# rs485_ISO_IO.net
KiCad netlist of a schematic drawn in EAGLE
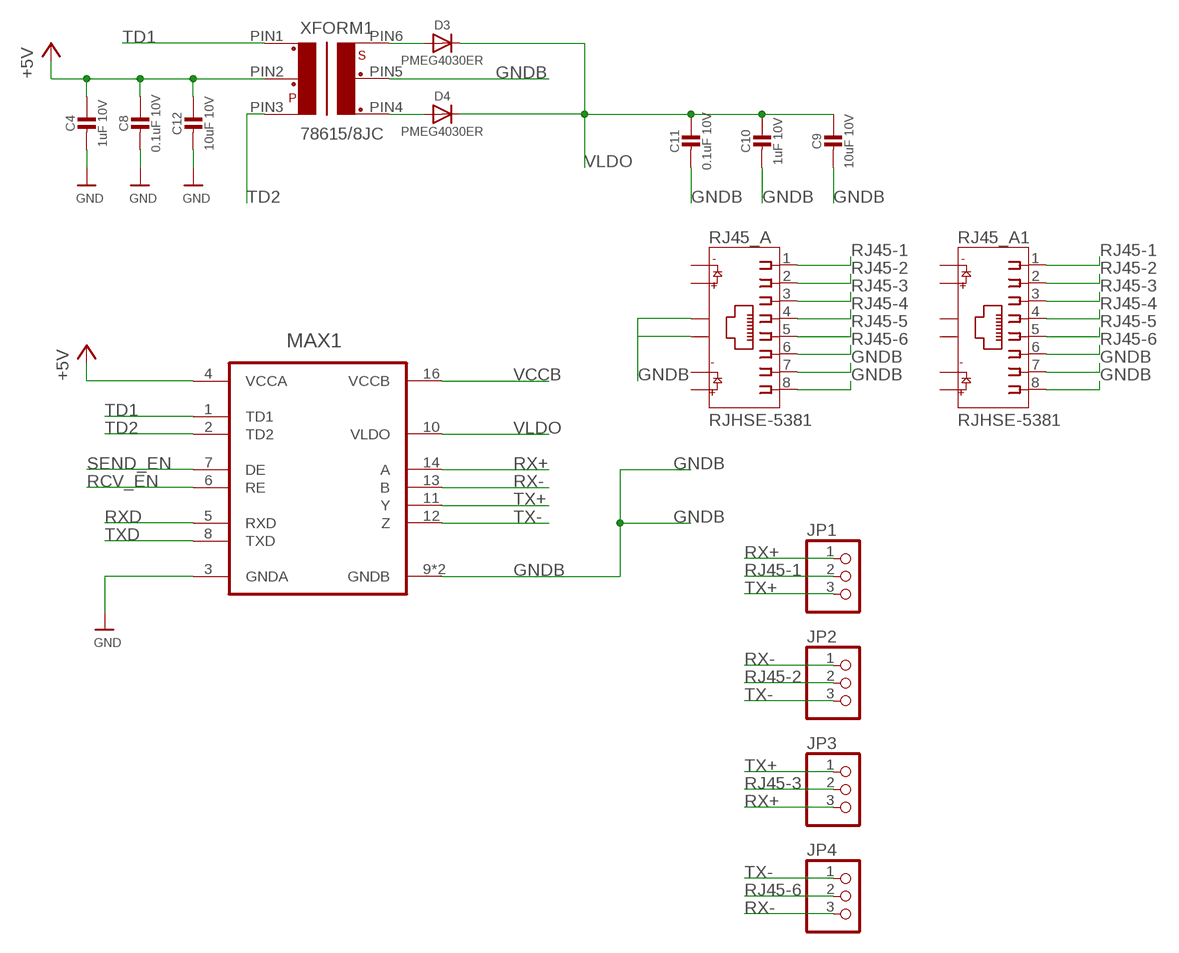
[diagram p0: schematic, sheet 1]

(export (version "E")
  (design (tool "Eeschema 10.0.6"))
  (components
    (comp (ref "C4")
      (value "1uF 10V")
      (footprint "eagle-import:0603-MINI")
      (libsource (lib "eagle-import") (part "CAP_CERAMIC0603MINI"))
    )
    (comp (ref "C8")
      (value "0.1uF 10V")
      (footprint "eagle-import:0603-MINI")
      (libsource (lib "eagle-import") (part "CAP_CERAMIC0603MINI"))
    )
    (comp (ref "C9")
      (value "10uF 10V")
      (footprint "eagle-import:0603-MINI")
      (libsource (lib "eagle-import") (part "CAP_CERAMIC0603MINI"))
    )
    (comp (ref "C10")
      (value "1uF 10V")
      (footprint "eagle-import:0603-MINI")
      (libsource (lib "eagle-import") (part "CAP_CERAMIC0603MINI"))
    )
    (comp (ref "C11")
      (value "0.1uF 10V")
      (footprint "eagle-import:0603-MINI")
      (libsource (lib "eagle-import") (part "CAP_CERAMIC0603MINI"))
    )
    (comp (ref "C12")
      (value "10uF 10V")
      (footprint "eagle-import:0603-MINI")
      (libsource (lib "eagle-import") (part "CAP_CERAMIC0603MINI"))
    )
    (comp (ref "D3")
      (value "PMEG4030ER")
      (footprint "eagle-import:SOD-123")
      (libsource (lib "eagle-import") (part "DIODESOD-123"))
    )
    (comp (ref "D4")
      (value "PMEG4030ER")
      (footprint "eagle-import:SOD-123")
      (libsource (lib "eagle-import") (part "DIODESOD-123"))
    )
    (comp (ref "JP1")
      (value "PINHD-1X3")
      (footprint "eagle-import:1X03")
      (libsource (lib "eagle-import") (part "PINHD-1X3"))
    )
    (comp (ref "JP2")
      (value "PINHD-1X3")
      (footprint "eagle-import:1X03")
      (libsource (lib "eagle-import") (part "PINHD-1X3"))
    )
    (comp (ref "JP3")
      (value "PINHD-1X3")
      (footprint "eagle-import:1X03")
      (libsource (lib "eagle-import") (part "PINHD-1X3"))
    )
    (comp (ref "JP4")
      (value "PINHD-1X3")
      (footprint "eagle-import:1X03")
      (libsource (lib "eagle-import") (part "PINHD-1X3"))
    )
    (comp (ref "MAX1")
      (value "MAX14853GWE+")
      (footprint "eagle-import:SOIC127P1034X267-16N")
      (libsource (lib "eagle-import") (part "MAX14853GWE+"))
    )
    (comp (ref "RJ45_A")
      (value "RJHSE-5381")
      (footprint "eagle-import:AMPHENOL_RJHSE-5381")
      (fields (field (name "MF") "Amphenol"))
      (libsource (lib "eagle-import") (part "RJHSE-5381"))
    )
    (comp (ref "RJ45_A1")
      (value "RJHSE-5381")
      (footprint "eagle-import:AMPHENOL_RJHSE-5381")
      (fields (field (name "MF") "Amphenol"))
      (libsource (lib "eagle-import") (part "RJHSE-5381"))
    )
    (comp (ref "XFORM1")
      (value "78615/8JC")
      (footprint "eagle-import:0.1_SMD")
      (libsource (lib "eagle-import") (part "78615/8JC"))
    )
  )
  (nets
    (net (code "1") (name "+5V") (class "Default")
      (node (ref "C12") (pin "1") (pinfunction "1_1") (pintype "passive"))
      (node (ref "C4") (pin "1") (pinfunction "1_1") (pintype "passive"))
      (node (ref "C8") (pin "1") (pinfunction "1_1") (pintype "passive"))
      (node (ref "MAX1") (pin "4") (pinfunction "VCCA_4") (pintype "power_in"))
      (node (ref "XFORM1") (pin "PIN2") (pinfunction "2_PIN2") (pintype "passive"))
    )
    (net (code "2") (name "/GNDB") (class "Default")
      (node (ref "C10") (pin "2") (pinfunction "2_2") (pintype "passive"))
      (node (ref "C11") (pin "2") (pinfunction "2_2") (pintype "passive"))
      (node (ref "C9") (pin "2") (pinfunction "2_2") (pintype "passive"))
      (node (ref "MAX1") (pin "15") (pinfunction "GNDB_15") (pintype "bidirectional"))
      (node (ref "MAX1") (pin "9") (pinfunction "GNDB_9") (pintype "bidirectional"))
      (node (ref "RJ45_A") (pin "7") (pinfunction "7_7") (pintype "passive"))
      (node (ref "RJ45_A") (pin "8") (pinfunction "8_8") (pintype "passive"))
      (node (ref "RJ45_A") (pin "S1") (pinfunction "S1_S1") (pintype "passive"))
      (node (ref "RJ45_A") (pin "S2") (pinfunction "S2_S2") (pintype "passive"))
      (node (ref "RJ45_A1") (pin "7") (pinfunction "7_7") (pintype "passive"))
      (node (ref "RJ45_A1") (pin "8") (pinfunction "8_8") (pintype "passive"))
      (node (ref "XFORM1") (pin "PIN5") (pinfunction "5_PIN5") (pintype "passive"))
    )
    (net (code "3") (name "/RCV_EN") (class "Default")
      (node (ref "MAX1") (pin "6") (pinfunction "RE_6") (pintype "input"))
    )
    (net (code "4") (name "/RJ45-1") (class "Default")
      (node (ref "JP1") (pin "2") (pinfunction "2_2") (pintype "passive"))
      (node (ref "RJ45_A") (pin "1") (pinfunction "1_1") (pintype "passive"))
      (node (ref "RJ45_A1") (pin "1") (pinfunction "1_1") (pintype "passive"))
    )
    (net (code "5") (name "/RJ45-2") (class "Default")
      (node (ref "JP2") (pin "2") (pinfunction "2_2") (pintype "passive"))
      (node (ref "RJ45_A") (pin "2") (pinfunction "2_2") (pintype "passive"))
      (node (ref "RJ45_A1") (pin "2") (pinfunction "2_2") (pintype "passive"))
    )
    (net (code "6") (name "/RJ45-3") (class "Default")
      (node (ref "JP3") (pin "2") (pinfunction "2_2") (pintype "passive"))
      (node (ref "RJ45_A") (pin "3") (pinfunction "3_3") (pintype "passive"))
      (node (ref "RJ45_A1") (pin "3") (pinfunction "3_3") (pintype "passive"))
    )
    (net (code "7") (name "/RJ45-4") (class "Default")
      (node (ref "RJ45_A") (pin "4") (pinfunction "4_4") (pintype "passive"))
      (node (ref "RJ45_A1") (pin "4") (pinfunction "4_4") (pintype "passive"))
    )
    (net (code "8") (name "/RJ45-5") (class "Default")
      (node (ref "RJ45_A") (pin "5") (pinfunction "5_5") (pintype "passive"))
      (node (ref "RJ45_A1") (pin "5") (pinfunction "5_5") (pintype "passive"))
    )
    (net (code "9") (name "/RJ45-6") (class "Default")
      (node (ref "JP4") (pin "2") (pinfunction "2_2") (pintype "passive"))
      (node (ref "RJ45_A") (pin "6") (pinfunction "6_6") (pintype "passive"))
      (node (ref "RJ45_A1") (pin "6") (pinfunction "6_6") (pintype "passive"))
    )
    (net (code "10") (name "/RX+") (class "Default")
      (node (ref "JP1") (pin "1") (pinfunction "1_1") (pintype "passive"))
      (node (ref "JP3") (pin "3") (pinfunction "3_3") (pintype "passive"))
      (node (ref "MAX1") (pin "14") (pinfunction "A_14") (pintype "bidirectional"))
    )
    (net (code "11") (name "/RX-") (class "Default")
      (node (ref "JP2") (pin "1") (pinfunction "1_1") (pintype "passive"))
      (node (ref "JP4") (pin "3") (pinfunction "3_3") (pintype "passive"))
      (node (ref "MAX1") (pin "13") (pinfunction "B_13") (pintype "bidirectional"))
    )
    (net (code "12") (name "/RXD") (class "Default")
      (node (ref "MAX1") (pin "5") (pinfunction "RXD_5") (pintype "input"))
    )
    (net (code "13") (name "/SEND_EN") (class "Default")
      (node (ref "MAX1") (pin "7") (pinfunction "DE_7") (pintype "input"))
    )
    (net (code "14") (name "/TD1") (class "Default")
      (node (ref "MAX1") (pin "1") (pinfunction "TD1_1") (pintype "bidirectional"))
      (node (ref "XFORM1") (pin "PIN1") (pinfunction "1_PIN1") (pintype "passive"))
    )
    (net (code "15") (name "/TD2") (class "Default")
      (node (ref "MAX1") (pin "2") (pinfunction "TD2_2") (pintype "bidirectional"))
      (node (ref "XFORM1") (pin "PIN3") (pinfunction "3_PIN3") (pintype "passive"))
    )
    (net (code "16") (name "/TX+") (class "Default")
      (node (ref "JP1") (pin "3") (pinfunction "3_3") (pintype "passive"))
      (node (ref "JP3") (pin "1") (pinfunction "1_1") (pintype "passive"))
      (node (ref "MAX1") (pin "11") (pinfunction "Y_11") (pintype "bidirectional"))
    )
    (net (code "17") (name "/TX-") (class "Default")
      (node (ref "JP2") (pin "3") (pinfunction "3_3") (pintype "passive"))
      (node (ref "JP4") (pin "1") (pinfunction "1_1") (pintype "passive"))
      (node (ref "MAX1") (pin "12") (pinfunction "Z_12") (pintype "bidirectional"))
    )
    (net (code "18") (name "/TXD") (class "Default")
      (node (ref "MAX1") (pin "8") (pinfunction "TXD_8") (pintype "input"))
    )
    (net (code "19") (name "/VCCB") (class "Default")
      (node (ref "MAX1") (pin "16") (pinfunction "VCCB_16") (pintype "bidirectional"))
    )
    (net (code "20") (name "/VLDO") (class "Default")
      (node (ref "C10") (pin "1") (pinfunction "1_1") (pintype "passive"))
      (node (ref "C11") (pin "1") (pinfunction "1_1") (pintype "passive"))
      (node (ref "C9") (pin "1") (pinfunction "1_1") (pintype "passive"))
      (node (ref "D3") (pin "C") (pinfunction "C_C") (pintype "passive"))
      (node (ref "D4") (pin "C") (pinfunction "C_C") (pintype "passive"))
      (node (ref "MAX1") (pin "10") (pinfunction "VLDO_10") (pintype "output"))
    )
    (net (code "21") (name "GND") (class "Default")
      (node (ref "C12") (pin "2") (pinfunction "2_2") (pintype "passive"))
      (node (ref "C4") (pin "2") (pinfunction "2_2") (pintype "passive"))
      (node (ref "C8") (pin "2") (pinfunction "2_2") (pintype "passive"))
      (node (ref "MAX1") (pin "3") (pinfunction "GNDA_3") (pintype "passive"))
    )
    (net (code "22") (name "Net-(XFORM1-4)") (class "Default")
      (node (ref "D4") (pin "A") (pinfunction "A_A") (pintype "passive"))
      (node (ref "XFORM1") (pin "PIN4") (pinfunction "4_PIN4") (pintype "passive"))
    )
    (net (code "23") (name "Net-(XFORM1-6)") (class "Default")
      (node (ref "D3") (pin "A") (pinfunction "A_A") (pintype "passive"))
      (node (ref "XFORM1") (pin "PIN6") (pinfunction "6_PIN6") (pintype "passive"))
    )
    (net (code "24") (name "unconnected-(RJ45_A-Pad9)") (class "Default")
      (node (ref "RJ45_A") (pin "9") (pinfunction "9_9") (pintype "passive"))
    )
    (net (code "25") (name "unconnected-(RJ45_A-Pad10)") (class "Default")
      (node (ref "RJ45_A") (pin "10") (pinfunction "10_10") (pintype "passive"))
    )
    (net (code "26") (name "unconnected-(RJ45_A-Pad11)") (class "Default")
      (node (ref "RJ45_A") (pin "11") (pinfunction "11_11") (pintype "passive"))
    )
    (net (code "27") (name "unconnected-(RJ45_A-Pad12)") (class "Default")
      (node (ref "RJ45_A") (pin "12") (pinfunction "12_12") (pintype "passive"))
    )
    (net (code "28") (name "unconnected-(RJ45_A1-Pad9)") (class "Default")
      (node (ref "RJ45_A1") (pin "9") (pinfunction "9_9") (pintype "passive"))
    )
    (net (code "29") (name "unconnected-(RJ45_A1-Pad10)") (class "Default")
      (node (ref "RJ45_A1") (pin "10") (pinfunction "10_10") (pintype "passive"))
    )
    (net (code "30") (name "unconnected-(RJ45_A1-Pad11)") (class "Default")
      (node (ref "RJ45_A1") (pin "11") (pinfunction "11_11") (pintype "passive"))
    )
    (net (code "31") (name "unconnected-(RJ45_A1-Pad12)") (class "Default")
      (node (ref "RJ45_A1") (pin "12") (pinfunction "12_12") (pintype "passive"))
    )
    (net (code "32") (name "unconnected-(RJ45_A1-PadS1)") (class "Default")
      (node (ref "RJ45_A1") (pin "S1") (pinfunction "S1_S1") (pintype "passive"))
    )
    (net (code "33") (name "unconnected-(RJ45_A1-PadS2)") (class "Default")
      (node (ref "RJ45_A1") (pin "S2") (pinfunction "S2_S2") (pintype "passive"))
    )
  )
)
